# 1-Schematic_esp32.net
KiCad netlist of a schematic drawn in EasyEDA
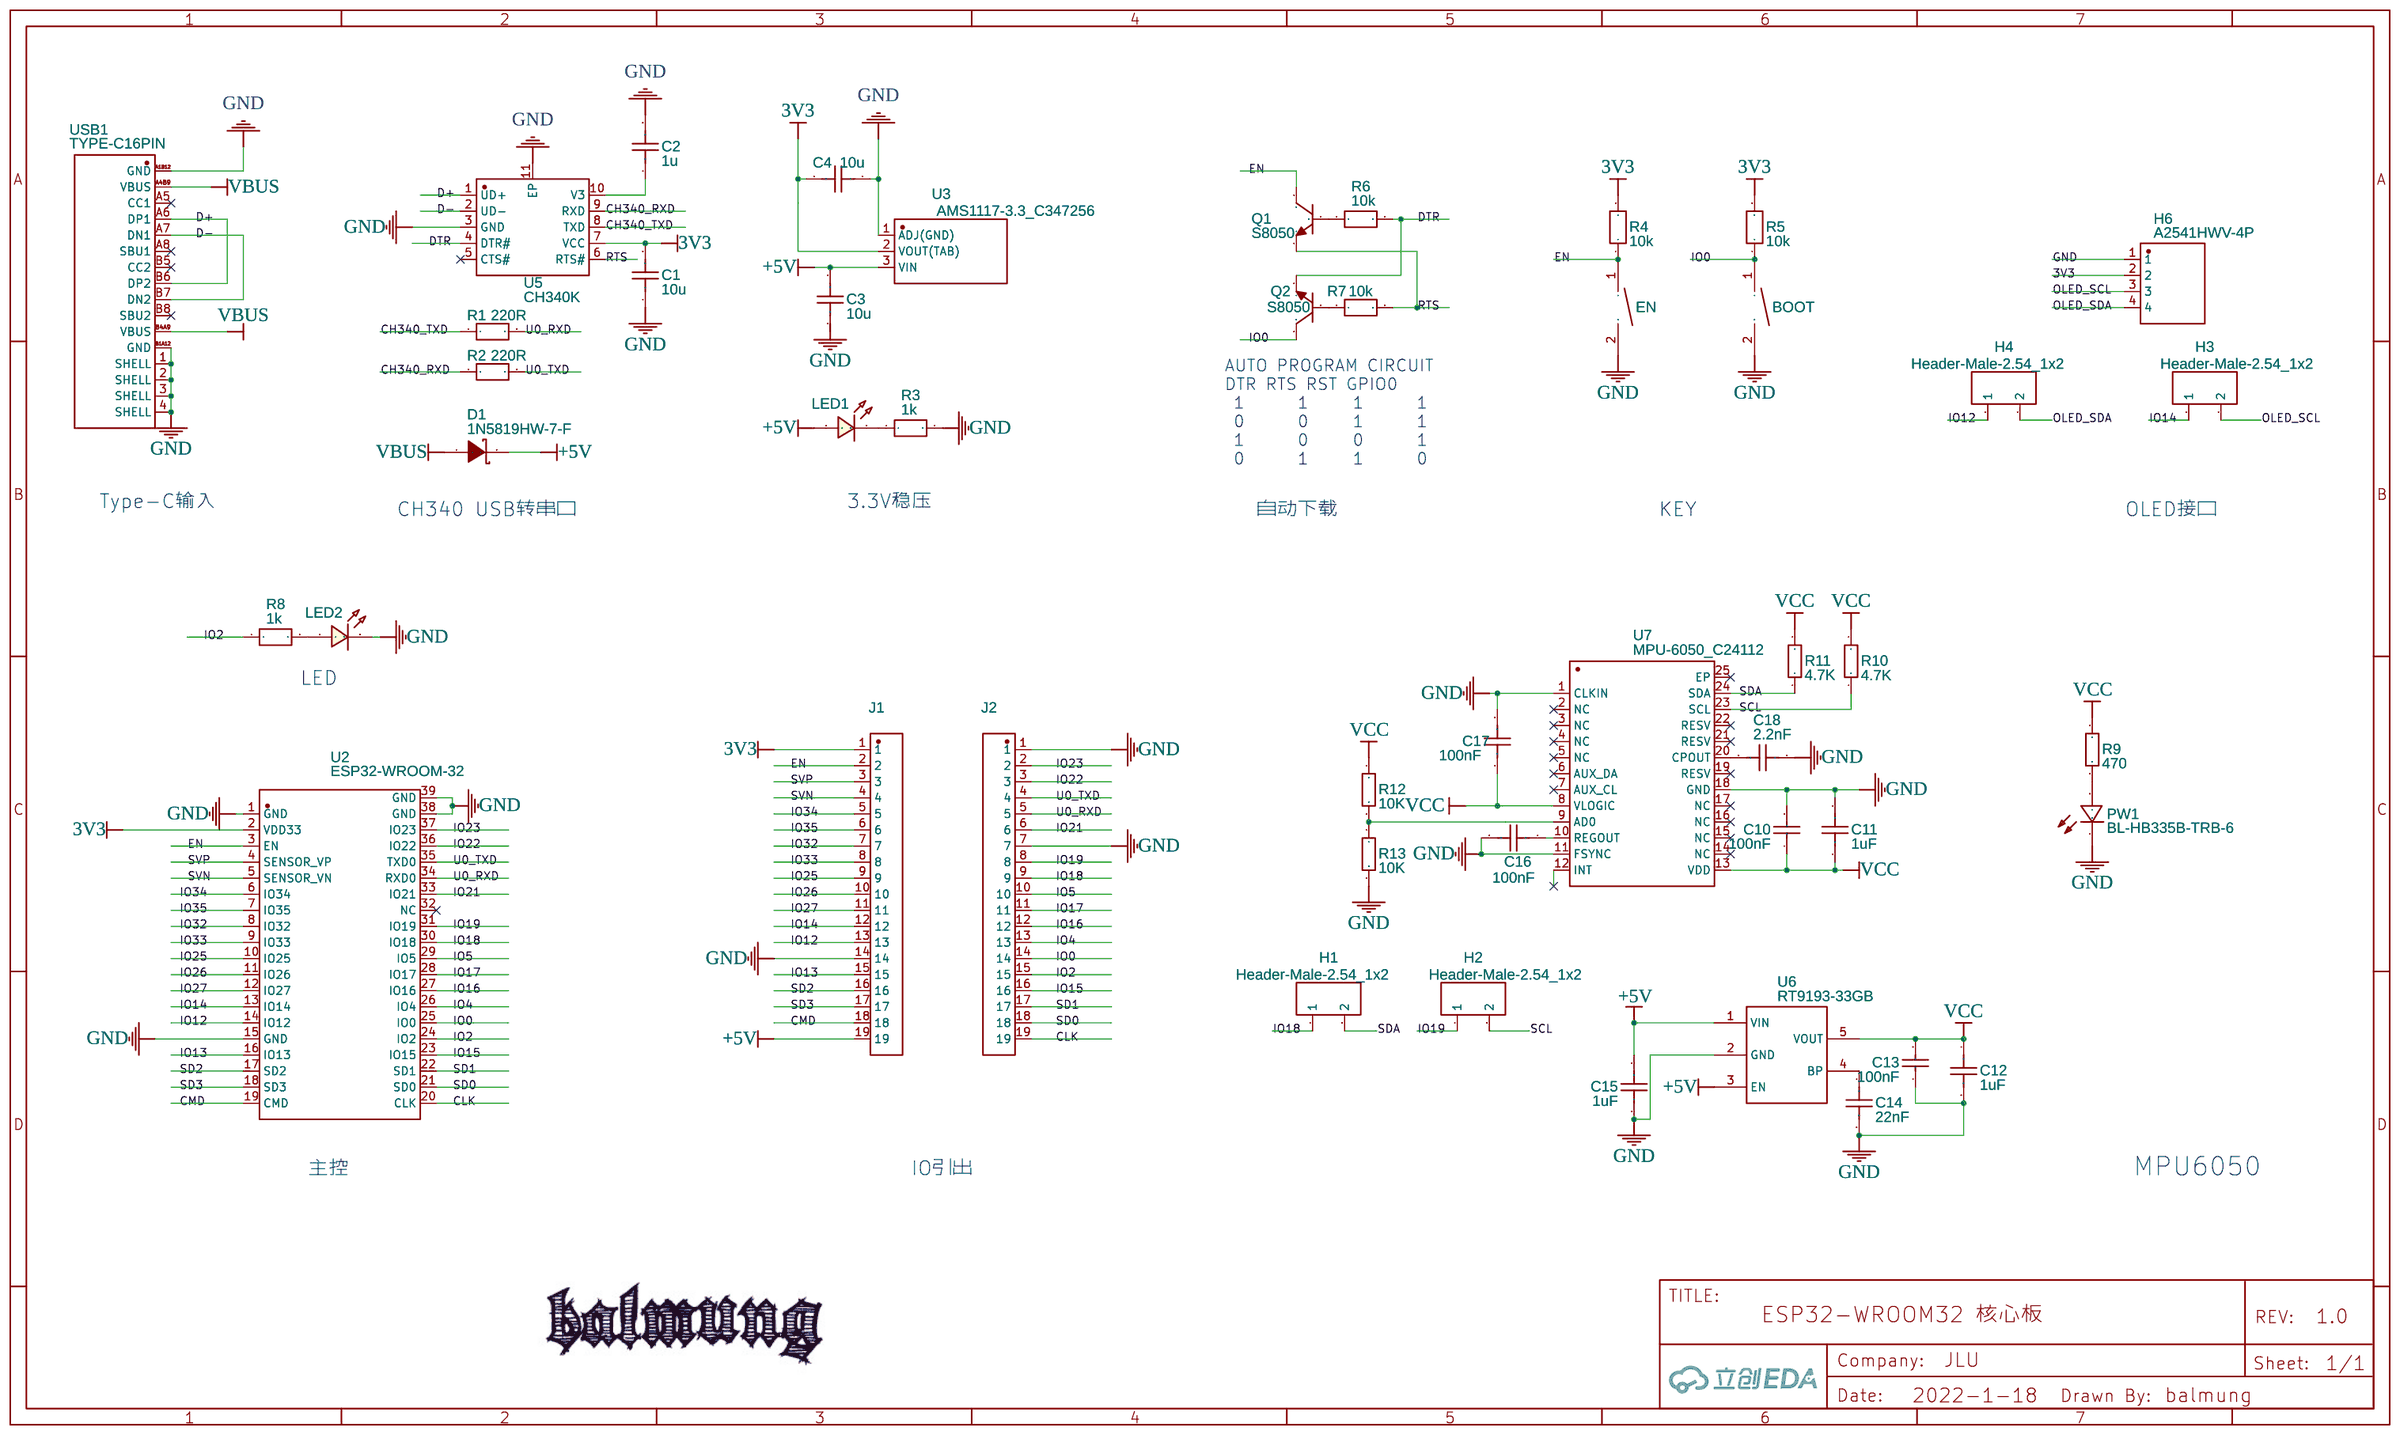
[diagram p0: schematic sheet]

(export (version "E")
  (design (tool "Eeschema 10.0.6"))
  (components
    (comp (ref "BOOT")
      (value "TSA343G00D-250J2")
      (fields (field (name "BOM_Supplier Part") "C354947"))
      (libsource (lib "") (part "TSA343G00D-250J2"))
    )
    (comp (ref "C1") (value "10u") (libsource (lib "") (part "C_0603_US_2")))
    (comp (ref "C2") (value "1u") (libsource (lib "") (part "C_0603_US_2")))
    (comp (ref "C3") (value "10u") (libsource (lib "") (part "C_0603_US")))
    (comp (ref "C4") (value "10u") (libsource (lib "") (part "C_0603_US_1")))
    (comp (ref "C10")
      (value "100nF")
      (fields
        (field (name "BOM_Manufacturer Part") "CT41G-0603-2X1-50V-0.1μF-K(N)")
        (field (name "BOM_Supplier Part") "C125205")
      )
      (libsource (lib "") (part "CT41G-0603-2X1-50V-0.1μF-K(N)"))
    )
    (comp (ref "C11")
      (value "1uF")
      (fields
        (field (name "BOM_Manufacturer Part") "GRM185R61E105KA12D")
        (field (name "BOM_Supplier Part") "C162200")
      )
      (libsource (lib "") (part "GRM185R61E105KA12D_1"))
    )
    (comp (ref "C12")
      (value "1uF")
      (fields
        (field (name "BOM_Manufacturer Part") "GRM185R61E105KA12D")
        (field (name "BOM_Supplier Part") "C162200")
      )
      (libsource (lib "") (part "GRM185R61E105KA12D_1"))
    )
    (comp (ref "C13")
      (value "100nF")
      (fields
        (field (name "BOM_Manufacturer Part") "CT41G-0603-2X1-50V-0.1μF-K(N)")
        (field (name "BOM_Supplier Part") "C125205")
      )
      (libsource (lib "") (part "CT41G-0603-2X1-50V-0.1μF-K(N)"))
    )
    (comp (ref "C14")
      (value "22nF")
      (fields
        (field (name "BOM_Manufacturer Part") "0603B223K500CT")
        (field (name "BOM_Supplier Part") "C302021")
      )
      (libsource (lib "") (part "0603B223K500CT"))
    )
    (comp (ref "C15")
      (value "1uF")
      (fields
        (field (name "BOM_Manufacturer Part") "GRM185R61E105KA12D")
        (field (name "BOM_Supplier Part") "C162200")
      )
      (libsource (lib "") (part "GRM185R61E105KA12D"))
    )
    (comp (ref "C16")
      (value "100nF")
      (fields
        (field (name "BOM_Manufacturer Part") "CC0603KRX7R9BB104")
        (field (name "BOM_Supplier Part") "C14663")
      )
      (libsource (lib "") (part "CC0603KRX7R9BB104_1"))
    )
    (comp (ref "C17")
      (value "100nF")
      (fields
        (field (name "BOM_Manufacturer Part") "CC0603KRX7R9BB104")
        (field (name "BOM_Supplier Part") "C14663")
      )
      (libsource (lib "") (part "CC0603KRX7R9BB104"))
    )
    (comp (ref "C18")
      (value "2.2nF")
      (fields
        (field (name "BOM_Manufacturer Part") "CS0603KRX7R9BB222")
        (field (name "BOM_Supplier Part") "C309517")
      )
      (libsource (lib "") (part "CS0603KRX7R9BB222"))
    )
    (comp (ref "D1")
      (value "1N5819HW-7-F")
      (fields (field (name "BOM_Supplier Part") "C82544"))
      (libsource (lib "") (part "1N5819HW-7-F"))
    )
    (comp (ref "EN")
      (value "TSA343G00D-250J2")
      (fields (field (name "BOM_Supplier Part") "C354947"))
      (libsource (lib "") (part "TSA343G00D-250J2_1"))
    )
    (comp (ref "H1")
      (value "Header-Male-2.54_1x2")
      (fields (field (name "BOM_Manufacturer Part") "826629-2") (field (name "BOM_Supplier Part") "C86471"))
      (libsource (lib "") (part "Header-Male-2.54_1x2"))
    )
    (comp (ref "H2")
      (value "Header-Male-2.54_1x2")
      (fields (field (name "BOM_Manufacturer Part") "826629-2") (field (name "BOM_Supplier Part") "C86471"))
      (libsource (lib "") (part "Header-Male-2.54_1x2"))
    )
    (comp (ref "H3")
      (value "Header-Male-2.54_1x2")
      (fields (field (name "BOM_Manufacturer Part") "826629-2") (field (name "BOM_Supplier Part") "C86471"))
      (libsource (lib "") (part "Header-Male-2.54_1x2"))
    )
    (comp (ref "H4")
      (value "Header-Male-2.54_1x2")
      (fields (field (name "BOM_Manufacturer Part") "826629-2") (field (name "BOM_Supplier Part") "C86471"))
      (libsource (lib "") (part "Header-Male-2.54_1x2"))
    )
    (comp (ref "H6")
      (value "A2541HWV-4P")
      (fields (field (name "BOM_Supplier Part") "C225501"))
      (libsource (lib "") (part "A2541HWV-4P"))
    )
    (comp (ref "J1")
      (value "Header-Male-2.54_1x19")
      (fields
        (field (name "BOM_Manufacturer Part") "2.54mm 1*20PHeader")
        (field (name "BOM_Supplier Part") "C50981")
      )
      (libsource (lib "") (part "Header-Male-2.54_1x19_1"))
    )
    (comp (ref "J2")
      (value "Header-Male-2.54_1x19")
      (fields
        (field (name "BOM_Manufacturer Part") "2.54mm 1*20PHeader")
        (field (name "BOM_Supplier Part") "C50981")
      )
      (libsource (lib "") (part "Header-Male-2.54_1x19"))
    )
    (comp (ref "LED1")
      (value "LED-0603_R")
      (fields
        (field (name "BOM_Manufacturer Part") "19-217/R6C-AL1M2VY/3T")
        (field (name "BOM_Supplier Part") "C72044")
      )
      (libsource (lib "") (part "LED-0603_R"))
    )
    (comp (ref "LED2")
      (value "LED-0603_R")
      (fields
        (field (name "BOM_Manufacturer Part") "19-217/R6C-AL1M2VY/3T")
        (field (name "BOM_Supplier Part") "C72044")
      )
      (libsource (lib "") (part "LED-0603_R"))
    )
    (comp (ref "PW1")
      (value "BL-HB335B-TRB-6")
      (fields (field (name "BOM_Supplier Part") "C189307"))
      (libsource (lib "") (part "BL-HB335B-TRB-6"))
    )
    (comp (ref "Q1")
      (value "S8050")
      (fields (field (name "BOM_Supplier Part") "C2688231"))
      (libsource (lib "") (part "S8050_1"))
    )
    (comp (ref "Q2")
      (value "S8050")
      (fields (field (name "BOM_Supplier Part") "C2688231"))
      (libsource (lib "") (part "S8050"))
    )
    (comp (ref "R1") (value "220R") (libsource (lib "") (part "R_0603_EU_1")))
    (comp (ref "R2") (value "220R") (libsource (lib "") (part "R_0603_EU_1")))
    (comp (ref "R3") (value "1k") (libsource (lib "") (part "R_0603_EU_1")))
    (comp (ref "R4") (value "10k") (libsource (lib "") (part "R_0603_EU")))
    (comp (ref "R5") (value "10k") (libsource (lib "") (part "R_0603_EU")))
    (comp (ref "R6") (value "10k") (libsource (lib "") (part "R_0603_EU_1")))
    (comp (ref "R7") (value "10k") (libsource (lib "") (part "R_0603_EU_1")))
    (comp (ref "R8") (value "1k") (libsource (lib "") (part "R_0603_EU_1")))
    (comp (ref "R9")
      (value "470")
      (fields
        (field (name "BOM_Manufacturer Part") "CR0805J80471G")
        (field (name "BOM_Supplier Part") "C102016")
      )
      (libsource (lib "") (part "CR0805J80471G"))
    )
    (comp (ref "R10")
      (value "4.7K")
      (fields
        (field (name "BOM_Manufacturer Part") "RMC08054.7K1%N")
        (field (name "BOM_Supplier Part") "C269746")
      )
      (libsource (lib "") (part "RMC08054.7K1%N"))
    )
    (comp (ref "R11")
      (value "4.7K")
      (fields
        (field (name "BOM_Manufacturer Part") "RMC08054.7K1%N")
        (field (name "BOM_Supplier Part") "C269746")
      )
      (libsource (lib "") (part "RMC08054.7K1%N"))
    )
    (comp (ref "R12")
      (value "10K")
      (fields
        (field (name "BOM_Manufacturer Part") "WR08X1002FTL")
        (field (name "BOM_Supplier Part") "C108451")
      )
      (libsource (lib "") (part "WR08X1002FTL"))
    )
    (comp (ref "R13")
      (value "10K")
      (fields
        (field (name "BOM_Manufacturer Part") "WR08X1002FTL")
        (field (name "BOM_Supplier Part") "C108451")
      )
      (libsource (lib "") (part "WR08X1002FTL"))
    )
    (comp (ref "U2")
      (value "ESP32-WROOM-32")
      (fields (field (name "BOM_Supplier Part") "C503587"))
      (libsource (lib "") (part "ESP32-WROOM-32"))
    )
    (comp (ref "U3")
      (value "AMS1117-3.3_C347256")
      (fields
        (field (name "BOM_Manufacturer Part") "AMS1117-3.3")
        (field (name "BOM_Supplier Part") "C347256")
      )
      (libsource (lib "") (part "AMS1117-3.3_C347256"))
    )
    (comp (ref "U5")
      (value "CH340K")
      (fields (field (name "BOM_Supplier Part") "C968586"))
      (libsource (lib "") (part "CH340K"))
    )
    (comp (ref "U6")
      (value "RT9193-33GB")
      (fields (field (name "BOM_Supplier Part") "C15651"))
      (libsource (lib "") (part "RT9193-33GB"))
    )
    (comp (ref "U7")
      (value "MPU-6050_C24112")
      (fields (field (name "BOM_Manufacturer Part") "MPU-6050") (field (name "BOM_Supplier Part") "C24112"))
      (libsource (lib "") (part "MPU-6050_C24112"))
    )
    (comp (ref "USB1")
      (value "TYPE-C16PIN")
      (fields (field (name "BOM_Supplier Part") "C393939"))
      (libsource (lib "") (part "TYPE-C16PIN"))
    )
  )
  (nets
    (net (code "1") (name "+5V") (class "Default")
      (node (ref "C15") (pin "1") (pinfunction "1_1") (pintype "unspecified"))
      (node (ref "C3") (pin "1") (pinfunction "1_1") (pintype "unspecified"))
      (node (ref "D1") (pin "2") (pinfunction "K_2") (pintype "unspecified"))
      (node (ref "J1") (pin "19") (pinfunction "19_19") (pintype "unspecified"))
      (node (ref "LED1") (pin "1") (pinfunction "1_1") (pintype "unspecified"))
      (node (ref "U3") (pin "3") (pinfunction "VIN_3") (pintype "unspecified"))
      (node (ref "U6") (pin "1") (pinfunction "VIN_1") (pintype "unspecified"))
      (node (ref "U6") (pin "3") (pinfunction "EN_3") (pintype "unspecified"))
    )
    (net (code "2") (name "/CH340_RXD") (class "Default")
      (node (ref "R2") (pin "1") (pinfunction "1_1") (pintype "unspecified"))
      (node (ref "U5") (pin "9") (pinfunction "RXD_9") (pintype "unspecified"))
    )
    (net (code "3") (name "/CH340_TXD") (class "Default")
      (node (ref "R1") (pin "1") (pinfunction "1_1") (pintype "unspecified"))
      (node (ref "U5") (pin "8") (pinfunction "TXD_8") (pintype "unspecified"))
    )
    (net (code "4") (name "/CLK") (class "Default")
      (node (ref "J2") (pin "19") (pinfunction "19_19") (pintype "unspecified"))
      (node (ref "U2") (pin "20") (pinfunction "CLK_20") (pintype "unspecified"))
    )
    (net (code "5") (name "/CMD") (class "Default")
      (node (ref "J1") (pin "18") (pinfunction "18_18") (pintype "unspecified"))
      (node (ref "U2") (pin "19") (pinfunction "CMD_19") (pintype "unspecified"))
    )
    (net (code "6") (name "/D+") (class "Default")
      (node (ref "U5") (pin "1") (pinfunction "UD+_1") (pintype "unspecified"))
      (node (ref "USB1") (pin "A6") (pinfunction "DP1_A6") (pintype "unspecified"))
      (node (ref "USB1") (pin "B6") (pinfunction "DP2_B6") (pintype "unspecified"))
    )
    (net (code "7") (name "/D-") (class "Default")
      (node (ref "U5") (pin "2") (pinfunction "UD-_2") (pintype "unspecified"))
      (node (ref "USB1") (pin "A7") (pinfunction "DN1_A7") (pintype "unspecified"))
      (node (ref "USB1") (pin "B7") (pinfunction "DN2_B7") (pintype "unspecified"))
    )
    (net (code "8") (name "/DTR") (class "Default")
      (node (ref "Q2") (pin "2") (pinfunction "E_2") (pintype "input"))
      (node (ref "R6") (pin "2") (pinfunction "2_2") (pintype "unspecified"))
      (node (ref "U5") (pin "4") (pinfunction "DTR#_4") (pintype "unspecified"))
    )
    (net (code "9") (name "/EN") (class "Default")
      (node (ref "EN") (pin "1") (pinfunction "1_1") (pintype "input"))
      (node (ref "J1") (pin "2") (pinfunction "2_2") (pintype "unspecified"))
      (node (ref "Q1") (pin "3") (pinfunction "C_3") (pintype "input"))
      (node (ref "R4") (pin "1") (pinfunction "1_1") (pintype "unspecified"))
      (node (ref "U2") (pin "3") (pinfunction "EN_3") (pintype "unspecified"))
    )
    (net (code "10") (name "/IO0") (class "Default")
      (node (ref "BOOT") (pin "1") (pinfunction "1_1") (pintype "input"))
      (node (ref "J2") (pin "14") (pinfunction "14_14") (pintype "unspecified"))
      (node (ref "Q2") (pin "3") (pinfunction "C_3") (pintype "input"))
      (node (ref "R5") (pin "1") (pinfunction "1_1") (pintype "unspecified"))
      (node (ref "U2") (pin "25") (pinfunction "IO0_25") (pintype "unspecified"))
    )
    (net (code "11") (name "/IO2") (class "Default")
      (node (ref "J2") (pin "15") (pinfunction "15_15") (pintype "unspecified"))
      (node (ref "R8") (pin "1") (pinfunction "1_1") (pintype "unspecified"))
      (node (ref "U2") (pin "24") (pinfunction "IO2_24") (pintype "unspecified"))
    )
    (net (code "12") (name "/IO4") (class "Default")
      (node (ref "J2") (pin "13") (pinfunction "13_13") (pintype "unspecified"))
      (node (ref "U2") (pin "26") (pinfunction "IO4_26") (pintype "unspecified"))
    )
    (net (code "13") (name "/IO5") (class "Default")
      (node (ref "J2") (pin "10") (pinfunction "10_10") (pintype "unspecified"))
      (node (ref "U2") (pin "29") (pinfunction "IO5_29") (pintype "unspecified"))
    )
    (net (code "14") (name "/IO12") (class "Default")
      (node (ref "H4") (pin "1") (pinfunction "1_1") (pintype "unspecified"))
      (node (ref "J1") (pin "13") (pinfunction "13_13") (pintype "unspecified"))
      (node (ref "U2") (pin "14") (pinfunction "IO12_14") (pintype "unspecified"))
    )
    (net (code "15") (name "/IO13") (class "Default")
      (node (ref "J1") (pin "15") (pinfunction "15_15") (pintype "unspecified"))
      (node (ref "U2") (pin "16") (pinfunction "IO13_16") (pintype "unspecified"))
    )
    (net (code "16") (name "/IO14") (class "Default")
      (node (ref "H3") (pin "1") (pinfunction "1_1") (pintype "unspecified"))
      (node (ref "J1") (pin "12") (pinfunction "12_12") (pintype "unspecified"))
      (node (ref "U2") (pin "13") (pinfunction "IO14_13") (pintype "unspecified"))
    )
    (net (code "17") (name "/IO15") (class "Default")
      (node (ref "J2") (pin "16") (pinfunction "16_16") (pintype "unspecified"))
      (node (ref "U2") (pin "23") (pinfunction "IO15_23") (pintype "unspecified"))
    )
    (net (code "18") (name "/IO16") (class "Default")
      (node (ref "J2") (pin "12") (pinfunction "12_12") (pintype "unspecified"))
      (node (ref "U2") (pin "27") (pinfunction "IO16_27") (pintype "unspecified"))
    )
    (net (code "19") (name "/IO17") (class "Default")
      (node (ref "J2") (pin "11") (pinfunction "11_11") (pintype "unspecified"))
      (node (ref "U2") (pin "28") (pinfunction "IO17_28") (pintype "unspecified"))
    )
    (net (code "20") (name "/IO18") (class "Default")
      (node (ref "H1") (pin "1") (pinfunction "1_1") (pintype "unspecified"))
      (node (ref "J2") (pin "9") (pinfunction "9_9") (pintype "unspecified"))
      (node (ref "U2") (pin "30") (pinfunction "IO18_30") (pintype "unspecified"))
    )
    (net (code "21") (name "/IO19") (class "Default")
      (node (ref "H2") (pin "1") (pinfunction "1_1") (pintype "unspecified"))
      (node (ref "J2") (pin "8") (pinfunction "8_8") (pintype "unspecified"))
      (node (ref "U2") (pin "31") (pinfunction "IO19_31") (pintype "unspecified"))
    )
    (net (code "22") (name "/IO21") (class "Default")
      (node (ref "J2") (pin "6") (pinfunction "6_6") (pintype "unspecified"))
      (node (ref "U2") (pin "33") (pinfunction "IO21_33") (pintype "unspecified"))
    )
    (net (code "23") (name "/IO22") (class "Default")
      (node (ref "J2") (pin "3") (pinfunction "3_3") (pintype "unspecified"))
      (node (ref "U2") (pin "36") (pinfunction "IO22_36") (pintype "unspecified"))
    )
    (net (code "24") (name "/IO23") (class "Default")
      (node (ref "J2") (pin "2") (pinfunction "2_2") (pintype "unspecified"))
      (node (ref "U2") (pin "37") (pinfunction "IO23_37") (pintype "unspecified"))
    )
    (net (code "25") (name "/IO25") (class "Default")
      (node (ref "J1") (pin "9") (pinfunction "9_9") (pintype "unspecified"))
      (node (ref "U2") (pin "10") (pinfunction "IO25_10") (pintype "unspecified"))
    )
    (net (code "26") (name "/IO26") (class "Default")
      (node (ref "J1") (pin "10") (pinfunction "10_10") (pintype "unspecified"))
      (node (ref "U2") (pin "11") (pinfunction "IO26_11") (pintype "unspecified"))
    )
    (net (code "27") (name "/IO27") (class "Default")
      (node (ref "J1") (pin "11") (pinfunction "11_11") (pintype "unspecified"))
      (node (ref "U2") (pin "12") (pinfunction "IO27_12") (pintype "unspecified"))
    )
    (net (code "28") (name "/IO32") (class "Default")
      (node (ref "J1") (pin "7") (pinfunction "7_7") (pintype "unspecified"))
      (node (ref "U2") (pin "8") (pinfunction "IO32_8") (pintype "unspecified"))
    )
    (net (code "29") (name "/IO33") (class "Default")
      (node (ref "J1") (pin "8") (pinfunction "8_8") (pintype "unspecified"))
      (node (ref "U2") (pin "9") (pinfunction "IO33_9") (pintype "unspecified"))
    )
    (net (code "30") (name "/IO34") (class "Default")
      (node (ref "J1") (pin "5") (pinfunction "5_5") (pintype "unspecified"))
      (node (ref "U2") (pin "6") (pinfunction "IO34_6") (pintype "unspecified"))
    )
    (net (code "31") (name "/IO35") (class "Default")
      (node (ref "J1") (pin "6") (pinfunction "6_6") (pintype "unspecified"))
      (node (ref "U2") (pin "7") (pinfunction "IO35_7") (pintype "unspecified"))
    )
    (net (code "32") (name "/OLED_SCL") (class "Default")
      (node (ref "H3") (pin "2") (pinfunction "2_2") (pintype "unspecified"))
      (node (ref "H6") (pin "3") (pinfunction "3_3") (pintype "unspecified"))
    )
    (net (code "33") (name "/OLED_SDA") (class "Default")
      (node (ref "H4") (pin "2") (pinfunction "2_2") (pintype "unspecified"))
      (node (ref "H6") (pin "4") (pinfunction "4_4") (pintype "unspecified"))
    )
    (net (code "34") (name "/RTS") (class "Default")
      (node (ref "Q1") (pin "2") (pinfunction "E_2") (pintype "input"))
      (node (ref "R7") (pin "2") (pinfunction "2_2") (pintype "unspecified"))
      (node (ref "U5") (pin "6") (pinfunction "RTS#_6") (pintype "unspecified"))
    )
    (net (code "35") (name "/SCL") (class "Default")
      (node (ref "H2") (pin "2") (pinfunction "2_2") (pintype "unspecified"))
      (node (ref "R10") (pin "1") (pinfunction "1_1") (pintype "unspecified"))
      (node (ref "U7") (pin "23") (pinfunction "SCL_23") (pintype "unspecified"))
    )
    (net (code "36") (name "/SD0") (class "Default")
      (node (ref "J2") (pin "18") (pinfunction "18_18") (pintype "unspecified"))
      (node (ref "U2") (pin "21") (pinfunction "SD0_21") (pintype "unspecified"))
    )
    (net (code "37") (name "/SD1") (class "Default")
      (node (ref "J2") (pin "17") (pinfunction "17_17") (pintype "unspecified"))
      (node (ref "U2") (pin "22") (pinfunction "SD1_22") (pintype "unspecified"))
    )
    (net (code "38") (name "/SD2") (class "Default")
      (node (ref "J1") (pin "16") (pinfunction "16_16") (pintype "unspecified"))
      (node (ref "U2") (pin "17") (pinfunction "SD2_17") (pintype "unspecified"))
    )
    (net (code "39") (name "/SD3") (class "Default")
      (node (ref "J1") (pin "17") (pinfunction "17_17") (pintype "unspecified"))
      (node (ref "U2") (pin "18") (pinfunction "SD3_18") (pintype "unspecified"))
    )
    (net (code "40") (name "/SDA") (class "Default")
      (node (ref "H1") (pin "2") (pinfunction "2_2") (pintype "unspecified"))
      (node (ref "R11") (pin "1") (pinfunction "1_1") (pintype "unspecified"))
      (node (ref "U7") (pin "24") (pinfunction "SDA_24") (pintype "unspecified"))
    )
    (net (code "41") (name "/SVN") (class "Default")
      (node (ref "J1") (pin "4") (pinfunction "4_4") (pintype "unspecified"))
      (node (ref "U2") (pin "5") (pinfunction "SENSOR_VN_5") (pintype "unspecified"))
    )
    (net (code "42") (name "/SVP") (class "Default")
      (node (ref "J1") (pin "3") (pinfunction "3_3") (pintype "unspecified"))
      (node (ref "U2") (pin "4") (pinfunction "SENSOR_VP_4") (pintype "unspecified"))
    )
    (net (code "43") (name "/U0_RXD") (class "Default")
      (node (ref "J2") (pin "5") (pinfunction "5_5") (pintype "unspecified"))
      (node (ref "R1") (pin "2") (pinfunction "2_2") (pintype "unspecified"))
      (node (ref "U2") (pin "34") (pinfunction "RXD0_34") (pintype "unspecified"))
    )
    (net (code "44") (name "/U0_TXD") (class "Default")
      (node (ref "J2") (pin "4") (pinfunction "4_4") (pintype "unspecified"))
      (node (ref "R2") (pin "2") (pinfunction "2_2") (pintype "unspecified"))
      (node (ref "U2") (pin "35") (pinfunction "TXD0_35") (pintype "unspecified"))
    )
    (net (code "45") (name "3V3") (class "Default")
      (node (ref "C1") (pin "2") (pinfunction "2_2") (pintype "unspecified"))
      (node (ref "C4") (pin "1") (pinfunction "1_1") (pintype "unspecified"))
      (node (ref "H6") (pin "2") (pinfunction "2_2") (pintype "unspecified"))
      (node (ref "J1") (pin "1") (pinfunction "1_1") (pintype "unspecified"))
      (node (ref "R4") (pin "2") (pinfunction "2_2") (pintype "unspecified"))
      (node (ref "R5") (pin "2") (pinfunction "2_2") (pintype "unspecified"))
      (node (ref "U2") (pin "2") (pinfunction "VDD33_2") (pintype "unspecified"))
      (node (ref "U3") (pin "2") (pinfunction "VOUT(TAB)_2") (pintype "unspecified"))
      (node (ref "U5") (pin "7") (pinfunction "VCC_7") (pintype "unspecified"))
    )
    (net (code "46") (name "GND") (class "Default")
      (node (ref "BOOT") (pin "2") (pinfunction "2_2") (pintype "input"))
      (node (ref "C1") (pin "1") (pinfunction "1_1") (pintype "unspecified"))
      (node (ref "C10") (pin "2") (pinfunction "2_2") (pintype "input"))
      (node (ref "C11") (pin "1") (pinfunction "1_1") (pintype "unspecified"))
      (node (ref "C12") (pin "2") (pinfunction "2_2") (pintype "unspecified"))
      (node (ref "C13") (pin "1") (pinfunction "1_1") (pintype "input"))
      (node (ref "C14") (pin "2") (pinfunction "2_2") (pintype "unspecified"))
      (node (ref "C15") (pin "2") (pinfunction "2_2") (pintype "unspecified"))
      (node (ref "C16") (pin "2") (pinfunction "2_2") (pintype "unspecified"))
      (node (ref "C17") (pin "2") (pinfunction "2_2") (pintype "unspecified"))
      (node (ref "C18") (pin "1") (pinfunction "1_1") (pintype "unspecified"))
      (node (ref "C2") (pin "2") (pinfunction "2_2") (pintype "unspecified"))
      (node (ref "C3") (pin "2") (pinfunction "2_2") (pintype "unspecified"))
      (node (ref "C4") (pin "2") (pinfunction "2_2") (pintype "unspecified"))
      (node (ref "EN") (pin "2") (pinfunction "2_2") (pintype "input"))
      (node (ref "H6") (pin "1") (pinfunction "1_1") (pintype "unspecified"))
      (node (ref "J1") (pin "14") (pinfunction "14_14") (pintype "unspecified"))
      (node (ref "J2") (pin "1") (pinfunction "1_1") (pintype "unspecified"))
      (node (ref "J2") (pin "7") (pinfunction "7_7") (pintype "unspecified"))
      (node (ref "LED2") (pin "2") (pinfunction "2_2") (pintype "unspecified"))
      (node (ref "PW1") (pin "1") (pinfunction "C_1") (pintype "unspecified"))
      (node (ref "R13") (pin "2") (pinfunction "2_2") (pintype "input"))
      (node (ref "R3") (pin "2") (pinfunction "2_2") (pintype "unspecified"))
      (node (ref "U2") (pin "1") (pinfunction "GND_1") (pintype "unspecified"))
      (node (ref "U2") (pin "15") (pinfunction "GND_15") (pintype "unspecified"))
      (node (ref "U2") (pin "38") (pinfunction "GND_38") (pintype "unspecified"))
      (node (ref "U2") (pin "39") (pinfunction "GND_39") (pintype "unspecified"))
      (node (ref "U3") (pin "1") (pinfunction "ADJ(GND)_1") (pintype "unspecified"))
      (node (ref "U5") (pin "11") (pinfunction "EP_11") (pintype "unspecified"))
      (node (ref "U5") (pin "3") (pinfunction "GND_3") (pintype "unspecified"))
      (node (ref "U6") (pin "2") (pinfunction "GND_2") (pintype "unspecified"))
      (node (ref "U7") (pin "1") (pinfunction "CLKIN_1") (pintype "unspecified"))
      (node (ref "U7") (pin "11") (pinfunction "FSYNC_11") (pintype "unspecified"))
      (node (ref "U7") (pin "18") (pinfunction "GND_18") (pintype "unspecified"))
      (node (ref "USB1") (pin "1") (pinfunction "SHELL_1") (pintype "unspecified"))
      (node (ref "USB1") (pin "2") (pinfunction "SHELL_2") (pintype "unspecified"))
      (node (ref "USB1") (pin "3") (pinfunction "SHELL_3") (pintype "unspecified"))
      (node (ref "USB1") (pin "4") (pinfunction "SHELL_4") (pintype "unspecified"))
      (node (ref "USB1") (pin "A1B12") (pinfunction "GND_A1B12") (pintype "unspecified"))
      (node (ref "USB1") (pin "B1A12") (pinfunction "GND_B1A12") (pintype "unspecified"))
    )
    (net (code "47") (name "Net-(LED1-Pad2)") (class "Default")
      (node (ref "LED1") (pin "2") (pinfunction "2_2") (pintype "unspecified"))
      (node (ref "R3") (pin "1") (pinfunction "1_1") (pintype "unspecified"))
    )
    (net (code "48") (name "Net-(LED2-Pad1)") (class "Default")
      (node (ref "LED2") (pin "1") (pinfunction "1_1") (pintype "unspecified"))
      (node (ref "R8") (pin "2") (pinfunction "2_2") (pintype "unspecified"))
    )
    (net (code "49") (name "Net-(PW1-A)") (class "Default")
      (node (ref "PW1") (pin "2") (pinfunction "A_2") (pintype "unspecified"))
      (node (ref "R9") (pin "1") (pinfunction "1_1") (pintype "input"))
    )
    (net (code "50") (name "Net-(Q1-B)") (class "Default")
      (node (ref "Q1") (pin "1") (pinfunction "B_1") (pintype "input"))
      (node (ref "R6") (pin "1") (pinfunction "1_1") (pintype "unspecified"))
    )
    (net (code "51") (name "Net-(Q2-B)") (class "Default")
      (node (ref "Q2") (pin "1") (pinfunction "B_1") (pintype "input"))
      (node (ref "R7") (pin "1") (pinfunction "1_1") (pintype "unspecified"))
    )
    (net (code "52") (name "Net-(U5-V3)") (class "Default")
      (node (ref "C2") (pin "1") (pinfunction "1_1") (pintype "unspecified"))
      (node (ref "U5") (pin "10") (pinfunction "V3_10") (pintype "unspecified"))
    )
    (net (code "53") (name "Net-(U6-BP)") (class "Default")
      (node (ref "C14") (pin "1") (pinfunction "1_1") (pintype "unspecified"))
      (node (ref "U6") (pin "4") (pinfunction "BP_4") (pintype "unspecified"))
    )
    (net (code "54") (name "Net-(U7-AD0)") (class "Default")
      (node (ref "R12") (pin "2") (pinfunction "2_2") (pintype "input"))
      (node (ref "R13") (pin "1") (pinfunction "1_1") (pintype "input"))
      (node (ref "U7") (pin "9") (pinfunction "AD0_9") (pintype "unspecified"))
    )
    (net (code "55") (name "Net-(U7-CPOUT)") (class "Default")
      (node (ref "C18") (pin "2") (pinfunction "2_2") (pintype "unspecified"))
      (node (ref "U7") (pin "20") (pinfunction "CPOUT_20") (pintype "unspecified"))
    )
    (net (code "56") (name "Net-(U7-REGOUT)") (class "Default")
      (node (ref "C16") (pin "1") (pinfunction "1_1") (pintype "unspecified"))
      (node (ref "U7") (pin "10") (pinfunction "REGOUT_10") (pintype "unspecified"))
    )
    (net (code "57") (name "VBUS") (class "Default")
      (node (ref "D1") (pin "1") (pinfunction "A_1") (pintype "unspecified"))
      (node (ref "USB1") (pin "A4B9") (pinfunction "VBUS_A4B9") (pintype "unspecified"))
      (node (ref "USB1") (pin "B4A9") (pinfunction "VBUS_B4A9") (pintype "unspecified"))
    )
    (net (code "58") (name "VCC") (class "Default")
      (node (ref "C10") (pin "1") (pinfunction "1_1") (pintype "input"))
      (node (ref "C11") (pin "2") (pinfunction "2_2") (pintype "unspecified"))
      (node (ref "C12") (pin "1") (pinfunction "1_1") (pintype "unspecified"))
      (node (ref "C13") (pin "2") (pinfunction "2_2") (pintype "input"))
      (node (ref "C17") (pin "1") (pinfunction "1_1") (pintype "unspecified"))
      (node (ref "R10") (pin "2") (pinfunction "2_2") (pintype "unspecified"))
      (node (ref "R11") (pin "2") (pinfunction "2_2") (pintype "unspecified"))
      (node (ref "R12") (pin "1") (pinfunction "1_1") (pintype "input"))
      (node (ref "R9") (pin "2") (pinfunction "2_2") (pintype "input"))
      (node (ref "U6") (pin "5") (pinfunction "VOUT_5") (pintype "unspecified"))
      (node (ref "U7") (pin "13") (pinfunction "VDD_13") (pintype "unspecified"))
      (node (ref "U7") (pin "8") (pinfunction "VLOGIC_8") (pintype "unspecified"))
    )
    (net (code "59") (name "unconnected-(U2-NC-Pad32)") (class "Default")
      (node (ref "U2") (pin "32") (pinfunction "NC_32") (pintype "unspecified+no_connect"))
    )
    (net (code "60") (name "unconnected-(U5-CTS#-Pad5)") (class "Default")
      (node (ref "U5") (pin "5") (pinfunction "CTS#_5") (pintype "unspecified+no_connect"))
    )
    (net (code "61") (name "unconnected-(U7-AUX_CL-Pad7)") (class "Default")
      (node (ref "U7") (pin "7") (pinfunction "AUX_CL_7") (pintype "unspecified+no_connect"))
    )
    (net (code "62") (name "unconnected-(U7-AUX_DA-Pad6)") (class "Default")
      (node (ref "U7") (pin "6") (pinfunction "AUX_DA_6") (pintype "unspecified+no_connect"))
    )
    (net (code "63") (name "unconnected-(U7-EP-Pad25)") (class "Default")
      (node (ref "U7") (pin "25") (pinfunction "EP_25") (pintype "unspecified+no_connect"))
    )
    (net (code "64") (name "unconnected-(U7-INT-Pad12)") (class "Default")
      (node (ref "U7") (pin "12") (pinfunction "INT_12") (pintype "unspecified+no_connect"))
    )
    (net (code "65") (name "unconnected-(U7-NC-Pad2)") (class "Default")
      (node (ref "U7") (pin "2") (pinfunction "NC_2") (pintype "unspecified+no_connect"))
    )
    (net (code "66") (name "unconnected-(U7-NC-Pad3)") (class "Default")
      (node (ref "U7") (pin "3") (pinfunction "NC_3") (pintype "unspecified+no_connect"))
    )
    (net (code "67") (name "unconnected-(U7-NC-Pad4)") (class "Default")
      (node (ref "U7") (pin "4") (pinfunction "NC_4") (pintype "unspecified+no_connect"))
    )
    (net (code "68") (name "unconnected-(U7-NC-Pad5)") (class "Default")
      (node (ref "U7") (pin "5") (pinfunction "NC_5") (pintype "unspecified+no_connect"))
    )
    (net (code "69") (name "unconnected-(U7-NC-Pad14)") (class "Default")
      (node (ref "U7") (pin "14") (pinfunction "NC_14") (pintype "unspecified+no_connect"))
    )
    (net (code "70") (name "unconnected-(U7-NC-Pad15)") (class "Default")
      (node (ref "U7") (pin "15") (pinfunction "NC_15") (pintype "unspecified+no_connect"))
    )
    (net (code "71") (name "unconnected-(U7-NC-Pad16)") (class "Default")
      (node (ref "U7") (pin "16") (pinfunction "NC_16") (pintype "unspecified+no_connect"))
    )
    (net (code "72") (name "unconnected-(U7-NC-Pad17)") (class "Default")
      (node (ref "U7") (pin "17") (pinfunction "NC_17") (pintype "unspecified+no_connect"))
    )
    (net (code "73") (name "unconnected-(U7-RESV-Pad19)") (class "Default")
      (node (ref "U7") (pin "19") (pinfunction "RESV_19") (pintype "unspecified+no_connect"))
    )
    (net (code "74") (name "unconnected-(U7-RESV-Pad21)") (class "Default")
      (node (ref "U7") (pin "21") (pinfunction "RESV_21") (pintype "unspecified+no_connect"))
    )
    (net (code "75") (name "unconnected-(U7-RESV-Pad22)") (class "Default")
      (node (ref "U7") (pin "22") (pinfunction "RESV_22") (pintype "unspecified+no_connect"))
    )
    (net (code "76") (name "unconnected-(USB1-CC1-PadA5)") (class "Default")
      (node (ref "USB1") (pin "A5") (pinfunction "CC1_A5") (pintype "unspecified+no_connect"))
    )
    (net (code "77") (name "unconnected-(USB1-CC2-PadB5)") (class "Default")
      (node (ref "USB1") (pin "B5") (pinfunction "CC2_B5") (pintype "unspecified+no_connect"))
    )
    (net (code "78") (name "unconnected-(USB1-SBU1-PadA8)") (class "Default")
      (node (ref "USB1") (pin "A8") (pinfunction "SBU1_A8") (pintype "unspecified+no_connect"))
    )
    (net (code "79") (name "unconnected-(USB1-SBU2-PadB8)") (class "Default")
      (node (ref "USB1") (pin "B8") (pinfunction "SBU2_B8") (pintype "unspecified+no_connect"))
    )
  )
)
